# THB6064.net
KiCad netlist of a schematic drawn in EAGLE
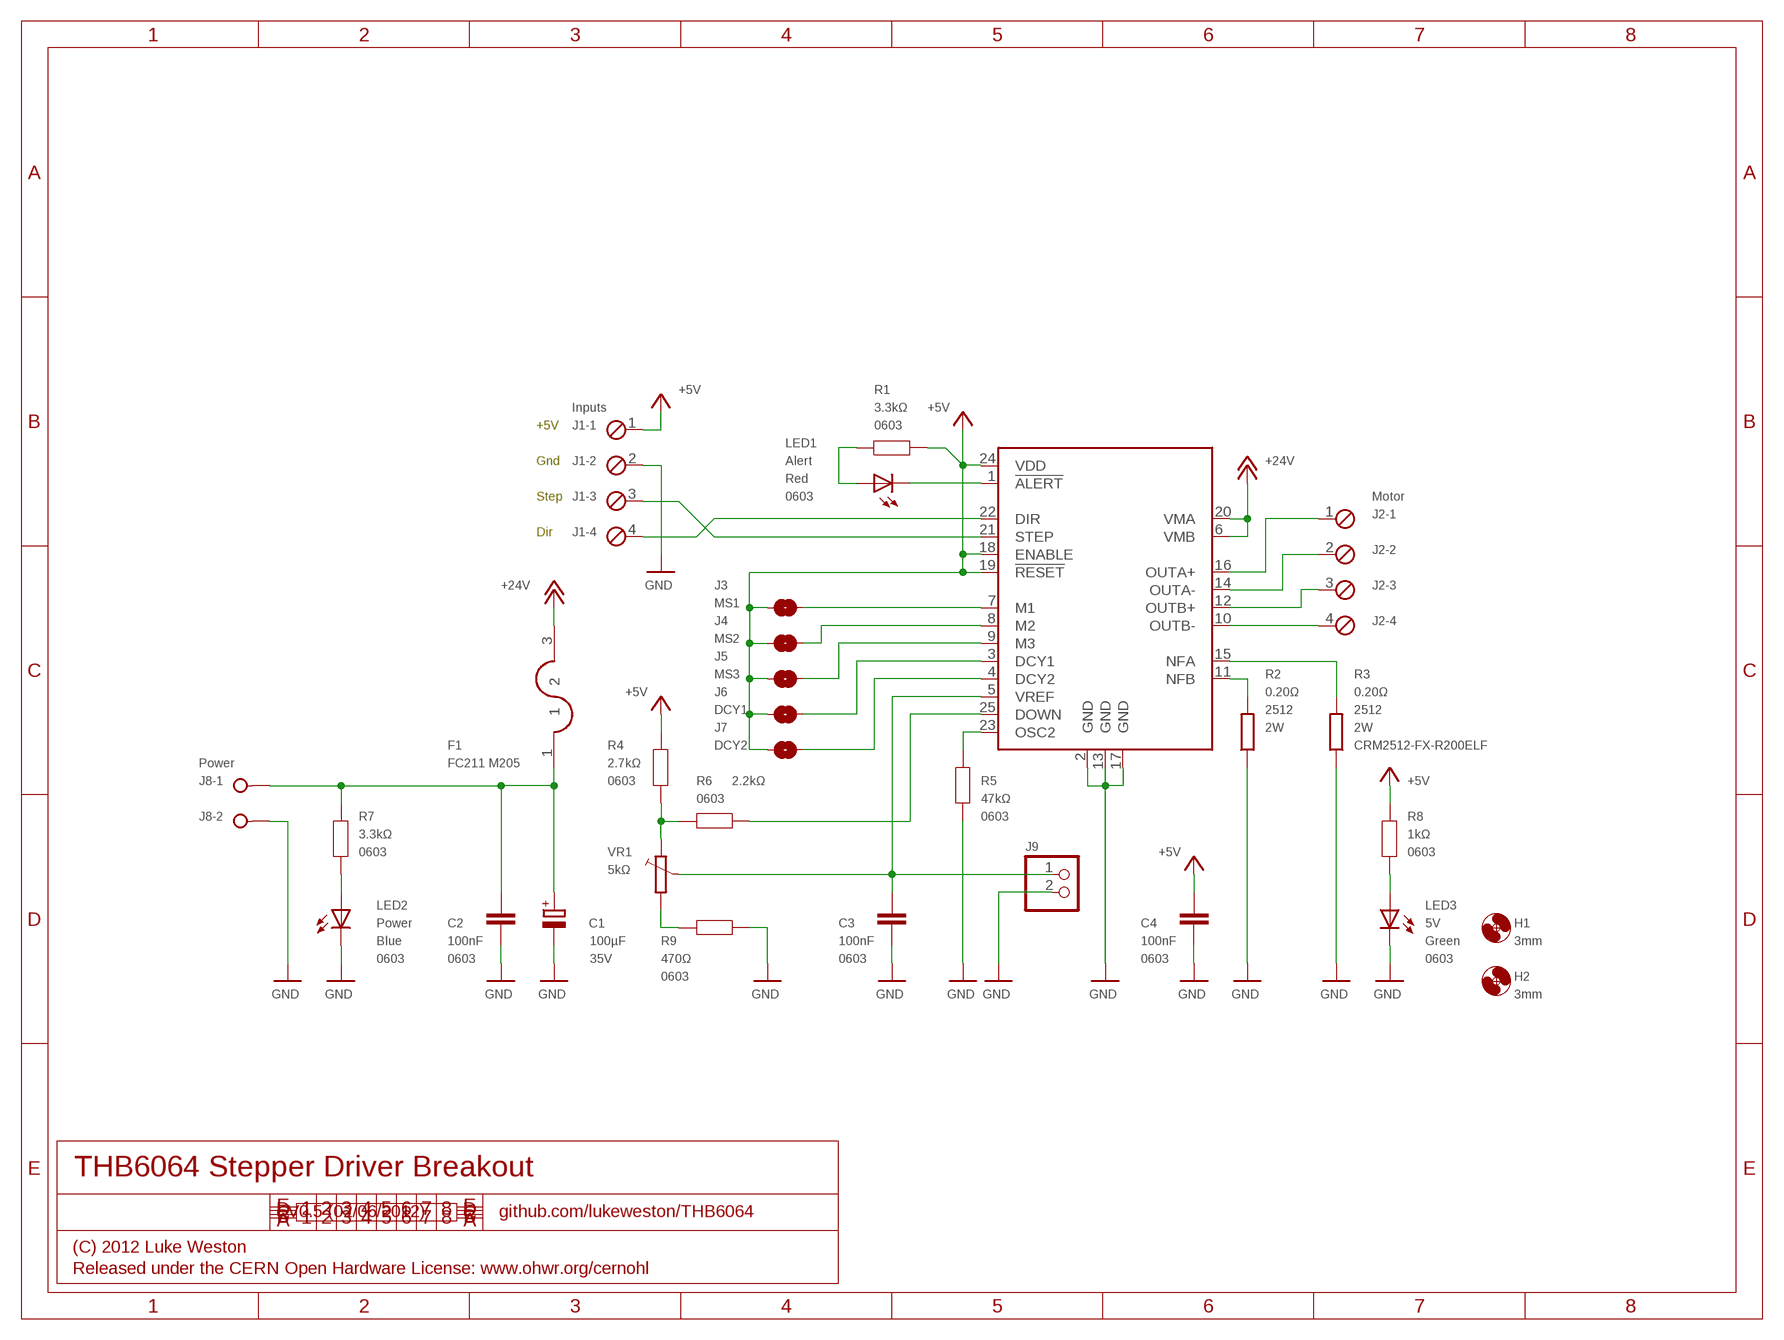
[diagram p0: schematic, sheet 1]

(export (version "E")
  (design (tool "Eeschema 10.0.6"))
  (components
    (comp (ref "C1")
      (value "100µF")
      (footprint "eagle-import:E3,5-8")
      (fields (field (name "VOLTAGE") "35V"))
      (libsource (lib "eagle-import") (part "CPOL-EUE3.5-8"))
    )
    (comp (ref "C2")
      (value "100nF")
      (footprint "eagle-import:0603")
      (fields (field (name "PACKAGE") "0603"))
      (libsource (lib "eagle-import") (part "CAP0603"))
    )
    (comp (ref "C3")
      (value "100nF")
      (footprint "eagle-import:0603")
      (fields (field (name "PACKAGE") "0603"))
      (libsource (lib "eagle-import") (part "CAP0603"))
    )
    (comp (ref "C4")
      (value "100nF")
      (footprint "eagle-import:0603")
      (fields (field (name "PACKAGE") "0603"))
      (libsource (lib "eagle-import") (part "CAP0603"))
    )
    (comp (ref "F1")
      (value "FC211 M205")
      (footprint "eagle-import:FUSE_5MM")
      (libsource (lib "eagle-import") (part "FUSEX20MM"))
    )
    (comp (ref "H1")
      (value "3mm")
      (footprint "eagle-import:3,0")
      (libsource (lib "eagle-import") (part "MOUNT-HOLE3.0"))
    )
    (comp (ref "H2")
      (value "3mm")
      (footprint "eagle-import:3,0")
      (libsource (lib "eagle-import") (part "MOUNT-HOLE3.0"))
    )
    (comp (ref "IC1")
      (value "THB6064")
      (footprint "eagle-import:ZIP25")
      (libsource (lib "eagle-import") (part "THB6064"))
    )
    (comp (ref "J1")
      (value "Inputs")
      (footprint "eagle-import:4POL254")
      (fields (field (name "OC_FARNELL") "unknown") (field (name "OC_NEWARK") "unknown"))
      (libsource (lib "eagle-import") (part "MPT4"))
    )
    (comp (ref "J2")
      (value "Motor")
      (footprint "eagle-import:4POL254")
      (fields (field (name "OC_FARNELL") "unknown") (field (name "OC_NEWARK") "unknown"))
      (libsource (lib "eagle-import") (part "MPT4"))
    )
    (comp (ref "J3") (value "MS1") (footprint "eagle-import:SJ") (libsource (lib "eagle-import") (part "SJ")))
    (comp (ref "J4") (value "MS2") (footprint "eagle-import:SJ") (libsource (lib "eagle-import") (part "SJ")))
    (comp (ref "J5") (value "MS3") (footprint "eagle-import:SJ") (libsource (lib "eagle-import") (part "SJ")))
    (comp (ref "J6")
      (value "DCY1")
      (footprint "eagle-import:SJ")
      (libsource (lib "eagle-import") (part "SJ"))
    )
    (comp (ref "J7")
      (value "DCY2")
      (footprint "eagle-import:SJ")
      (libsource (lib "eagle-import") (part "SJ"))
    )
    (comp (ref "J8")
      (value "Power")
      (footprint "eagle-import:W237-132")
      (libsource (lib "eagle-import") (part "W237-02P"))
    )
    (comp (ref "J9")
      (value "PINHD-1X2")
      (footprint "eagle-import:1X02")
      (libsource (lib "eagle-import") (part "PINHD-1X2"))
    )
    (comp (ref "LED1")
      (value "Alert")
      (footprint "eagle-import:LED-0603")
      (fields (field (name "COLOR") "Red") (field (name "PACKAGE") "0603"))
      (libsource (lib "eagle-import") (part "LED0603"))
    )
    (comp (ref "LED2")
      (value "Power")
      (footprint "eagle-import:LED-0603")
      (fields (field (name "COLOR") "Blue") (field (name "PACKAGE") "0603"))
      (libsource (lib "eagle-import") (part "LED0603"))
    )
    (comp (ref "LED3")
      (value "5V")
      (footprint "eagle-import:LED-0603")
      (fields (field (name "COLOR") "Green") (field (name "PACKAGE") "0603"))
      (libsource (lib "eagle-import") (part "LED0603"))
    )
    (comp (ref "R1")
      (value "3.3kΩ")
      (footprint "eagle-import:0603")
      (fields (field (name "PACKAGE") "0603"))
      (libsource (lib "eagle-import") (part "RESISTOR0603"))
    )
    (comp (ref "R2")
      (value "0.20Ω")
      (footprint "eagle-import:R2512")
      (fields (field (name "PACKAGE") "2512") (field (name "POWER") "2W"))
      (libsource (lib "eagle-import") (part "R-EU_R2512"))
    )
    (comp (ref "R3")
      (value "0.20Ω")
      (footprint "eagle-import:R2512")
      (fields
        (field (name "PACKAGE") "2512")
        (field (name "POWER") "2W")
        (field (name "SKU") "CRM2512-FX-R200ELF")
      )
      (libsource (lib "eagle-import") (part "R-EU_R2512"))
    )
    (comp (ref "R4")
      (value "2.7kΩ")
      (footprint "eagle-import:0603")
      (fields (field (name "PACKAGE") "0603"))
      (libsource (lib "eagle-import") (part "RESISTOR0603"))
    )
    (comp (ref "R5")
      (value "47kΩ")
      (footprint "eagle-import:0603")
      (fields (field (name "PACKAGE") "0603"))
      (libsource (lib "eagle-import") (part "RESISTOR0603"))
    )
    (comp (ref "R6")
      (value "2.2kΩ")
      (footprint "eagle-import:0603")
      (fields (field (name "PACKAGE") "0603"))
      (libsource (lib "eagle-import") (part "RESISTOR0603"))
    )
    (comp (ref "R7")
      (value "3.3kΩ")
      (footprint "eagle-import:0603")
      (fields (field (name "PACKAGE") "0603"))
      (libsource (lib "eagle-import") (part "RESISTOR0603"))
    )
    (comp (ref "R8")
      (value "1kΩ")
      (footprint "eagle-import:0603")
      (fields (field (name "PACKAGE") "0603"))
      (libsource (lib "eagle-import") (part "RESISTOR0603"))
    )
    (comp (ref "R9")
      (value "470Ω")
      (footprint "eagle-import:0603")
      (fields (field (name "PACKAGE") "0603"))
      (libsource (lib "eagle-import") (part "RESISTOR0603"))
    )
    (comp (ref "VR1")
      (value "5kΩ")
      (footprint "eagle-import:CT6")
      (libsource (lib "eagle-import") (part "TRIM_EU-CT6"))
    )
  )
  (nets
    (net (code "1") (name "+5V") (class "Default")
      (node (ref "C4") (pin "1") (pinfunction "1_1") (pintype "passive"))
      (node (ref "IC1") (pin "18") (pinfunction "ENABLE_18") (pintype "bidirectional"))
      (node (ref "IC1") (pin "19") (pinfunction "~{RESET}_19") (pintype "bidirectional"))
      (node (ref "IC1") (pin "24") (pinfunction "VDD_24") (pintype "bidirectional"))
      (node (ref "J1") (pin "1") (pinfunction "1_1") (pintype "passive"))
      (node (ref "J3") (pin "1") (pinfunction "1_1") (pintype "passive"))
      (node (ref "J4") (pin "1") (pinfunction "1_1") (pintype "passive"))
      (node (ref "J5") (pin "1") (pinfunction "1_1") (pintype "passive"))
      (node (ref "J6") (pin "1") (pinfunction "1_1") (pintype "passive"))
      (node (ref "J7") (pin "1") (pinfunction "1_1") (pintype "passive"))
      (node (ref "R1") (pin "2") (pinfunction "2_2") (pintype "passive"))
      (node (ref "R4") (pin "2") (pinfunction "2_2") (pintype "passive"))
      (node (ref "R8") (pin "2") (pinfunction "2_2") (pintype "passive"))
    )
    (net (code "2") (name "+24V") (class "Default")
      (node (ref "F1") (pin "3") (pinfunction "2_3") (pintype "bidirectional"))
      (node (ref "IC1") (pin "20") (pinfunction "VMA_20") (pintype "bidirectional"))
      (node (ref "IC1") (pin "6") (pinfunction "VMB_6") (pintype "bidirectional"))
    )
    (net (code "3") (name "GND") (class "Default")
      (node (ref "C1") (pin "-") (pinfunction "-_-") (pintype "passive"))
      (node (ref "C2") (pin "2") (pinfunction "2_2") (pintype "passive"))
      (node (ref "C3") (pin "2") (pinfunction "2_2") (pintype "passive"))
      (node (ref "C4") (pin "2") (pinfunction "2_2") (pintype "passive"))
      (node (ref "IC1") (pin "13") (pinfunction "GND_13") (pintype "bidirectional"))
      (node (ref "IC1") (pin "17") (pinfunction "GND_17") (pintype "bidirectional"))
      (node (ref "IC1") (pin "2") (pinfunction "GND_2") (pintype "bidirectional"))
      (node (ref "J1") (pin "2") (pinfunction "1_2") (pintype "passive"))
      (node (ref "J8") (pin "2") (pinfunction "KL_2") (pintype "passive"))
      (node (ref "J9") (pin "2") (pinfunction "2_2") (pintype "passive"))
      (node (ref "LED2") (pin "C") (pinfunction "C_C") (pintype "passive"))
      (node (ref "LED3") (pin "C") (pinfunction "C_C") (pintype "passive"))
      (node (ref "R2") (pin "1") (pinfunction "1_1") (pintype "passive"))
      (node (ref "R3") (pin "1") (pinfunction "1_1") (pintype "passive"))
      (node (ref "R5") (pin "1") (pinfunction "1_1") (pintype "passive"))
      (node (ref "R9") (pin "1") (pinfunction "1_1") (pintype "passive"))
    )
    (net (code "4") (name "Net-(IC1-DCY1)") (class "Default")
      (node (ref "IC1") (pin "3") (pinfunction "DCY1_3") (pintype "bidirectional"))
      (node (ref "J6") (pin "2") (pinfunction "2_2") (pintype "passive"))
    )
    (net (code "5") (name "Net-(IC1-DCY2)") (class "Default")
      (node (ref "IC1") (pin "4") (pinfunction "DCY2_4") (pintype "bidirectional"))
      (node (ref "J7") (pin "2") (pinfunction "2_2") (pintype "passive"))
    )
    (net (code "6") (name "Net-(IC1-DIR)") (class "Default")
      (node (ref "IC1") (pin "22") (pinfunction "DIR_22") (pintype "bidirectional"))
      (node (ref "J1") (pin "4") (pinfunction "1_4") (pintype "passive"))
    )
    (net (code "7") (name "Net-(IC1-DOWN)") (class "Default")
      (node (ref "IC1") (pin "25") (pinfunction "DOWN_25") (pintype "bidirectional"))
      (node (ref "R6") (pin "1") (pinfunction "1_1") (pintype "passive"))
    )
    (net (code "8") (name "Net-(IC1-M1)") (class "Default")
      (node (ref "IC1") (pin "7") (pinfunction "M1_7") (pintype "bidirectional"))
      (node (ref "J3") (pin "2") (pinfunction "2_2") (pintype "passive"))
    )
    (net (code "9") (name "Net-(IC1-M2)") (class "Default")
      (node (ref "IC1") (pin "8") (pinfunction "M2_8") (pintype "bidirectional"))
      (node (ref "J4") (pin "2") (pinfunction "2_2") (pintype "passive"))
    )
    (net (code "10") (name "Net-(IC1-M3)") (class "Default")
      (node (ref "IC1") (pin "9") (pinfunction "M3_9") (pintype "bidirectional"))
      (node (ref "J5") (pin "2") (pinfunction "2_2") (pintype "passive"))
    )
    (net (code "11") (name "Net-(IC1-NFA)") (class "Default")
      (node (ref "IC1") (pin "15") (pinfunction "NFA_15") (pintype "bidirectional"))
      (node (ref "R3") (pin "2") (pinfunction "2_2") (pintype "passive"))
    )
    (net (code "12") (name "Net-(IC1-NFB)") (class "Default")
      (node (ref "IC1") (pin "11") (pinfunction "NFB_11") (pintype "bidirectional"))
      (node (ref "R2") (pin "2") (pinfunction "2_2") (pintype "passive"))
    )
    (net (code "13") (name "Net-(IC1-OSC2)") (class "Default")
      (node (ref "IC1") (pin "23") (pinfunction "OSC2_23") (pintype "bidirectional"))
      (node (ref "R5") (pin "2") (pinfunction "2_2") (pintype "passive"))
    )
    (net (code "14") (name "Net-(IC1-OUTA+)") (class "Default")
      (node (ref "IC1") (pin "16") (pinfunction "OUTA+_16") (pintype "bidirectional"))
      (node (ref "J2") (pin "1") (pinfunction "1_1") (pintype "passive"))
    )
    (net (code "15") (name "Net-(IC1-OUTA-)") (class "Default")
      (node (ref "IC1") (pin "14") (pinfunction "OUTA-_14") (pintype "bidirectional"))
      (node (ref "J2") (pin "2") (pinfunction "1_2") (pintype "passive"))
    )
    (net (code "16") (name "Net-(IC1-OUTB+)") (class "Default")
      (node (ref "IC1") (pin "12") (pinfunction "OUTB+_12") (pintype "bidirectional"))
      (node (ref "J2") (pin "3") (pinfunction "1_3") (pintype "passive"))
    )
    (net (code "17") (name "Net-(IC1-OUTB-)") (class "Default")
      (node (ref "IC1") (pin "10") (pinfunction "OUTB-_10") (pintype "bidirectional"))
      (node (ref "J2") (pin "4") (pinfunction "1_4") (pintype "passive"))
    )
    (net (code "18") (name "Net-(IC1-STEP)") (class "Default")
      (node (ref "IC1") (pin "21") (pinfunction "STEP_21") (pintype "bidirectional"))
      (node (ref "J1") (pin "3") (pinfunction "1_3") (pintype "passive"))
    )
    (net (code "19") (name "Net-(IC1-VREF)") (class "Default")
      (node (ref "C3") (pin "1") (pinfunction "1_1") (pintype "passive"))
      (node (ref "IC1") (pin "5") (pinfunction "VREF_5") (pintype "bidirectional"))
      (node (ref "J9") (pin "1") (pinfunction "1_1") (pintype "passive"))
      (node (ref "VR1") (pin "S") (pinfunction "S_S") (pintype "passive"))
    )
    (net (code "20") (name "Net-(IC1-~{ALERT})") (class "Default")
      (node (ref "IC1") (pin "1") (pinfunction "~{ALERT}_1") (pintype "bidirectional"))
      (node (ref "LED1") (pin "C") (pinfunction "C_C") (pintype "passive"))
    )
    (net (code "21") (name "Net-(J8A-KL)") (class "Default")
      (node (ref "C1") (pin "+") (pinfunction "+_+") (pintype "passive"))
      (node (ref "C2") (pin "1") (pinfunction "1_1") (pintype "passive"))
      (node (ref "F1") (pin "1") (pinfunction "1_1") (pintype "bidirectional"))
      (node (ref "J8") (pin "1") (pinfunction "KL_1") (pintype "passive"))
      (node (ref "R7") (pin "2") (pinfunction "2_2") (pintype "passive"))
    )
    (net (code "22") (name "Net-(LED1-PadA)") (class "Default")
      (node (ref "LED1") (pin "A") (pinfunction "A_A") (pintype "passive"))
      (node (ref "R1") (pin "1") (pinfunction "1_1") (pintype "passive"))
    )
    (net (code "23") (name "Net-(LED2-PadA)") (class "Default")
      (node (ref "LED2") (pin "A") (pinfunction "A_A") (pintype "passive"))
      (node (ref "R7") (pin "1") (pinfunction "1_1") (pintype "passive"))
    )
    (net (code "24") (name "Net-(LED3-PadA)") (class "Default")
      (node (ref "LED3") (pin "A") (pinfunction "A_A") (pintype "passive"))
      (node (ref "R8") (pin "1") (pinfunction "1_1") (pintype "passive"))
    )
    (net (code "25") (name "Net-(R4-Pad1)") (class "Default")
      (node (ref "R4") (pin "1") (pinfunction "1_1") (pintype "passive"))
      (node (ref "R6") (pin "2") (pinfunction "2_2") (pintype "passive"))
      (node (ref "VR1") (pin "E") (pinfunction "E_E") (pintype "passive"))
    )
    (net (code "26") (name "Net-(R9-Pad2)") (class "Default")
      (node (ref "R9") (pin "2") (pinfunction "2_2") (pintype "passive"))
      (node (ref "VR1") (pin "A") (pinfunction "A_A") (pintype "passive"))
    )
  )
)
